# Brainb.net
KiCad netlist of a schematic drawn in EAGLE
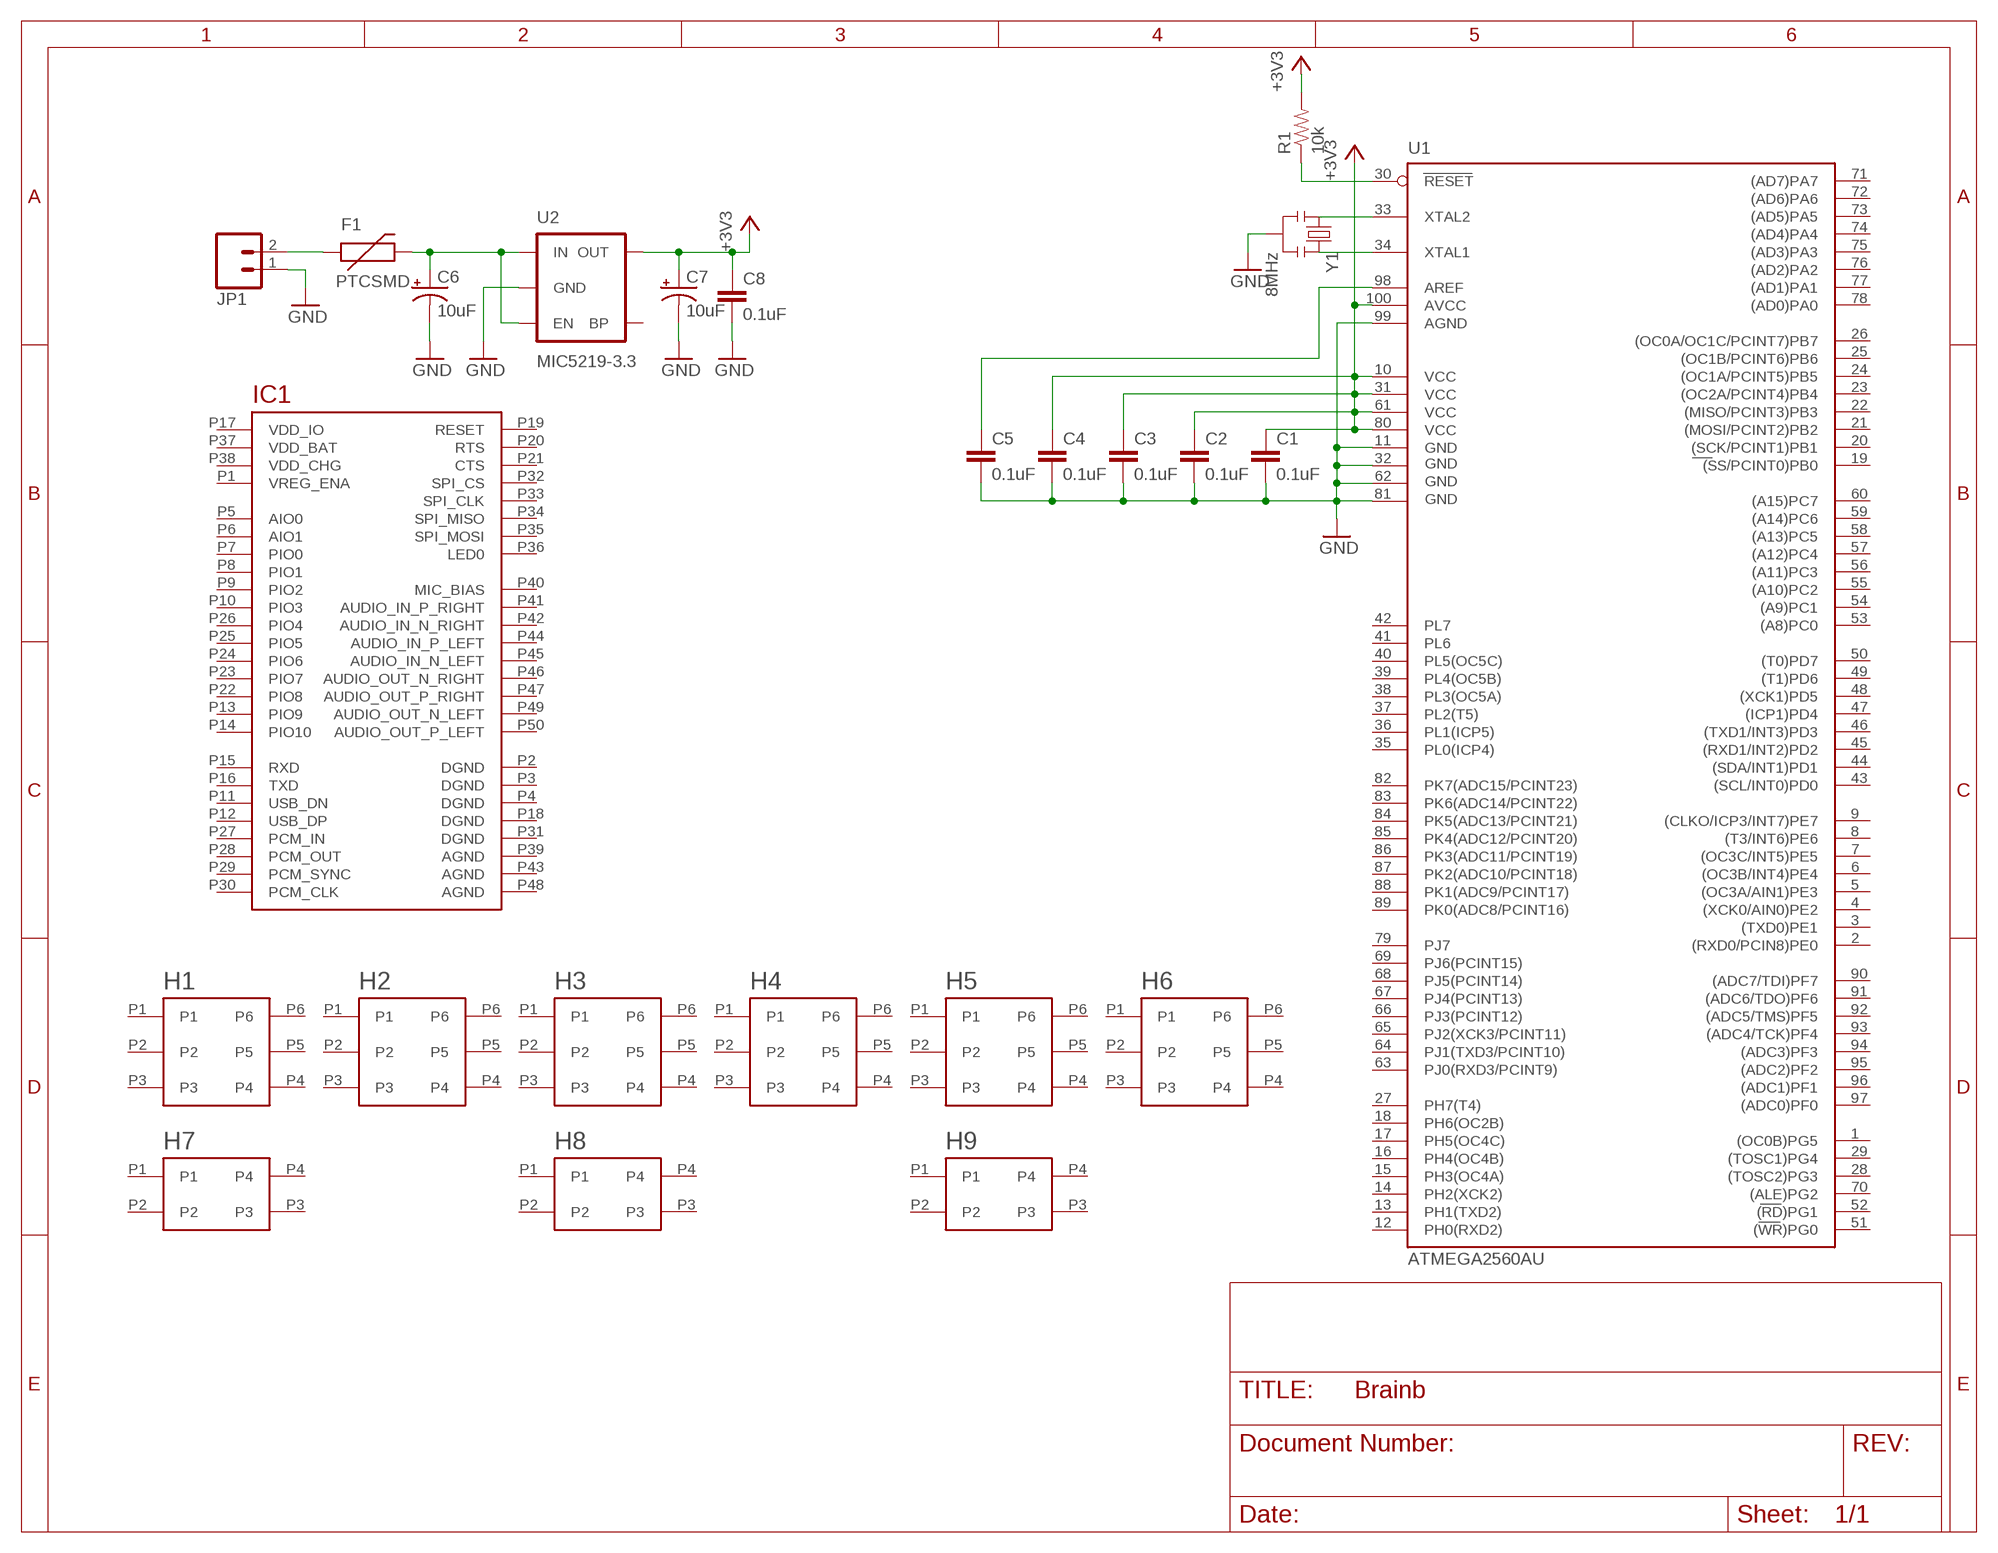
[diagram p0: schematic, sheet 1]

(export (version "E")
  (design (tool "Eeschema 10.0.6"))
  (components
    (comp (ref "C1")
      (value "0.1uF")
      (footprint "eagle-import:0603-CAP")
      (libsource (lib "eagle-import") (part "CAP0603-CAP"))
    )
    (comp (ref "C2")
      (value "0.1uF")
      (footprint "eagle-import:0603-CAP")
      (libsource (lib "eagle-import") (part "CAP0603-CAP"))
    )
    (comp (ref "C3")
      (value "0.1uF")
      (footprint "eagle-import:0603-CAP")
      (libsource (lib "eagle-import") (part "CAP0603-CAP"))
    )
    (comp (ref "C4")
      (value "0.1uF")
      (footprint "eagle-import:0603-CAP")
      (libsource (lib "eagle-import") (part "CAP0603-CAP"))
    )
    (comp (ref "C5")
      (value "0.1uF")
      (footprint "eagle-import:0603-CAP")
      (libsource (lib "eagle-import") (part "CAP0603-CAP"))
    )
    (comp (ref "C6")
      (value "10uF")
      (footprint "eagle-import:EIA3216")
      (libsource (lib "eagle-import") (part "CAP_POL1206"))
    )
    (comp (ref "C7")
      (value "10uF")
      (footprint "eagle-import:EIA3216")
      (libsource (lib "eagle-import") (part "CAP_POL1206"))
    )
    (comp (ref "C8")
      (value "0.1uF")
      (footprint "eagle-import:0603-CAP")
      (libsource (lib "eagle-import") (part "CAP0603-CAP"))
    )
    (comp (ref "F1")
      (value "PTCSMD")
      (footprint "eagle-import:PTC-1206")
      (libsource (lib "eagle-import") (part "PTCSMD"))
    )
    (comp (ref "H1")
      (value "3X2F_1MM_SMD")
      (footprint "eagle-import:3X2F_1MM_SMD")
      (libsource (lib "eagle-import") (part "3X2F_1MM_SMD"))
    )
    (comp (ref "H2")
      (value "3X2F_1MM_SMD")
      (footprint "eagle-import:3X2F_1MM_SMD")
      (libsource (lib "eagle-import") (part "3X2F_1MM_SMD"))
    )
    (comp (ref "H3")
      (value "3X2F_1MM_SMD")
      (footprint "eagle-import:3X2F_1MM_SMD")
      (libsource (lib "eagle-import") (part "3X2F_1MM_SMD"))
    )
    (comp (ref "H4")
      (value "3X2F_1MM_SMD")
      (footprint "eagle-import:3X2F_1MM_SMD")
      (libsource (lib "eagle-import") (part "3X2F_1MM_SMD"))
    )
    (comp (ref "H5")
      (value "3X2F_1MM_SMD")
      (footprint "eagle-import:3X2F_1MM_SMD")
      (libsource (lib "eagle-import") (part "3X2F_1MM_SMD"))
    )
    (comp (ref "H6")
      (value "3X2F_1MM_SMD")
      (footprint "eagle-import:3X2F_1MM_SMD")
      (libsource (lib "eagle-import") (part "3X2F_1MM_SMD"))
    )
    (comp (ref "H7")
      (value "2X2F_1MM_SMD")
      (footprint "eagle-import:2X2F_1MM_SMD")
      (libsource (lib "eagle-import") (part "2X2F_1MM_SMD"))
    )
    (comp (ref "H8")
      (value "2X2F_1MM_SMD")
      (footprint "eagle-import:2X2F_1MM_SMD")
      (libsource (lib "eagle-import") (part "2X2F_1MM_SMD"))
    )
    (comp (ref "H9")
      (value "2X2F_1MM_SMD")
      (footprint "eagle-import:2X2F_1MM_SMD")
      (libsource (lib "eagle-import") (part "2X2F_1MM_SMD"))
    )
    (comp (ref "IC1")
      (value "WT32WT32")
      (footprint "eagle-import:WT32")
      (libsource (lib "eagle-import") (part "WT32WT32"))
    )
    (comp (ref "JP1")
      (value "M02-JST-2MM-SMT")
      (footprint "eagle-import:JST-2-SMD")
      (libsource (lib "eagle-import") (part "M02-JST-2MM-SMT"))
    )
    (comp (ref "R1")
      (value "10k")
      (footprint "eagle-import:0603-RES")
      (libsource (lib "eagle-import") (part "RESISTOR0603-RES"))
    )
    (comp (ref "U1")
      (value "ATMEGA2560AU")
      (footprint "eagle-import:TQFP100")
      (libsource (lib "eagle-import") (part "ATMEGA2560AU"))
    )
    (comp (ref "U2")
      (value "MIC5219-3.3")
      (footprint "eagle-import:SOT23-5")
      (libsource (lib "eagle-import") (part "V_REG_MIC5219SMD"))
    )
    (comp (ref "Y1")
      (value "8MHz")
      (footprint "eagle-import:RESONATOR-SMD")
      (libsource (lib "eagle-import") (part "RESONATORSMD"))
    )
  )
  (nets
    (net (code "1") (name "+3V3") (class "Default")
      (node (ref "C1") (pin "1") (pinfunction "1_1") (pintype "passive"))
      (node (ref "C2") (pin "1") (pinfunction "1_1") (pintype "passive"))
      (node (ref "C3") (pin "1") (pinfunction "1_1") (pintype "passive"))
      (node (ref "C4") (pin "1") (pinfunction "1_1") (pintype "passive"))
      (node (ref "C7") (pin "A") (pinfunction "+_A") (pintype "passive"))
      (node (ref "C8") (pin "1") (pinfunction "1_1") (pintype "passive"))
      (node (ref "R1") (pin "2") (pinfunction "2_2") (pintype "passive"))
      (node (ref "U1") (pin "10") (pinfunction "VCC_10") (pintype "power_in"))
      (node (ref "U1") (pin "100") (pinfunction "AVCC_100") (pintype "power_in"))
      (node (ref "U1") (pin "31") (pinfunction "VCC1_31") (pintype "power_in"))
      (node (ref "U1") (pin "61") (pinfunction "VCC2_61") (pintype "power_in"))
      (node (ref "U1") (pin "80") (pinfunction "VCC3_80") (pintype "power_in"))
      (node (ref "U2") (pin "5") (pinfunction "OUT_5") (pintype "passive"))
    )
    (net (code "2") (name "GND") (class "Default")
      (node (ref "C1") (pin "2") (pinfunction "2_2") (pintype "passive"))
      (node (ref "C2") (pin "2") (pinfunction "2_2") (pintype "passive"))
      (node (ref "C3") (pin "2") (pinfunction "2_2") (pintype "passive"))
      (node (ref "C4") (pin "2") (pinfunction "2_2") (pintype "passive"))
      (node (ref "C5") (pin "2") (pinfunction "2_2") (pintype "passive"))
      (node (ref "C6") (pin "C") (pinfunction "-_C") (pintype "passive"))
      (node (ref "C7") (pin "C") (pinfunction "-_C") (pintype "passive"))
      (node (ref "C8") (pin "2") (pinfunction "2_2") (pintype "passive"))
      (node (ref "JP1") (pin "1") (pinfunction "2_1") (pintype "passive"))
      (node (ref "U1") (pin "11") (pinfunction "GND_11") (pintype "power_in"))
      (node (ref "U1") (pin "32") (pinfunction "GND1_32") (pintype "power_in"))
      (node (ref "U1") (pin "62") (pinfunction "GND2_62") (pintype "power_in"))
      (node (ref "U1") (pin "81") (pinfunction "GND3_81") (pintype "power_in"))
      (node (ref "U1") (pin "99") (pinfunction "AGND_99") (pintype "power_in"))
      (node (ref "U2") (pin "2") (pinfunction "GND_2") (pintype "input"))
      (node (ref "Y1") (pin "2") (pinfunction "2_2") (pintype "passive"))
    )
    (net (code "3") (name "Net-(C6-+)") (class "Default")
      (node (ref "C6") (pin "A") (pinfunction "+_A") (pintype "passive"))
      (node (ref "F1") (pin "2") (pinfunction "2_2") (pintype "bidirectional"))
      (node (ref "U2") (pin "1") (pinfunction "IN_1") (pintype "input"))
      (node (ref "U2") (pin "3") (pinfunction "EN_3") (pintype "input"))
    )
    (net (code "4") (name "Net-(JP1-1)") (class "Default")
      (node (ref "F1") (pin "1") (pinfunction "1_1") (pintype "bidirectional"))
      (node (ref "JP1") (pin "2") (pinfunction "1_2") (pintype "passive"))
    )
    (net (code "5") (name "Net-(U1-AREF)") (class "Default")
      (node (ref "C5") (pin "1") (pinfunction "1_1") (pintype "passive"))
      (node (ref "U1") (pin "98") (pinfunction "AREF_98") (pintype "bidirectional"))
    )
    (net (code "6") (name "Net-(U1-RESET)") (class "Default")
      (node (ref "R1") (pin "1") (pinfunction "1_1") (pintype "passive"))
      (node (ref "U1") (pin "30") (pinfunction "RESET_30") (pintype "input"))
    )
    (net (code "7") (name "Net-(U1-XTAL1)") (class "Default")
      (node (ref "U1") (pin "34") (pinfunction "XTAL1_34") (pintype "input"))
      (node (ref "Y1") (pin "3") (pinfunction "3_3") (pintype "passive"))
    )
    (net (code "8") (name "Net-(U1-XTAL2)") (class "Default")
      (node (ref "U1") (pin "33") (pinfunction "XTAL2_33") (pintype "output"))
      (node (ref "Y1") (pin "1") (pinfunction "1_1") (pintype "passive"))
    )
    (net (code "9") (name "unconnected-(H1-PadP1)") (class "Default")
      (node (ref "H1") (pin "P1") (pinfunction "P1_P1") (pintype "bidirectional"))
    )
    (net (code "10") (name "unconnected-(H1-PadP2)") (class "Default")
      (node (ref "H1") (pin "P2") (pinfunction "P2_P2") (pintype "bidirectional"))
    )
    (net (code "11") (name "unconnected-(H1-PadP3)") (class "Default")
      (node (ref "H1") (pin "P3") (pinfunction "P3_P3") (pintype "bidirectional"))
    )
    (net (code "12") (name "unconnected-(H1-PadP4)") (class "Default")
      (node (ref "H1") (pin "P4") (pinfunction "P4_P4") (pintype "bidirectional"))
    )
    (net (code "13") (name "unconnected-(H1-PadP5)") (class "Default")
      (node (ref "H1") (pin "P5") (pinfunction "P5_P5") (pintype "bidirectional"))
    )
    (net (code "14") (name "unconnected-(H1-PadP6)") (class "Default")
      (node (ref "H1") (pin "P6") (pinfunction "P6_P6") (pintype "bidirectional"))
    )
    (net (code "15") (name "unconnected-(H2-PadP1)") (class "Default")
      (node (ref "H2") (pin "P1") (pinfunction "P1_P1") (pintype "bidirectional"))
    )
    (net (code "16") (name "unconnected-(H2-PadP2)") (class "Default")
      (node (ref "H2") (pin "P2") (pinfunction "P2_P2") (pintype "bidirectional"))
    )
    (net (code "17") (name "unconnected-(H2-PadP3)") (class "Default")
      (node (ref "H2") (pin "P3") (pinfunction "P3_P3") (pintype "bidirectional"))
    )
    (net (code "18") (name "unconnected-(H2-PadP4)") (class "Default")
      (node (ref "H2") (pin "P4") (pinfunction "P4_P4") (pintype "bidirectional"))
    )
    (net (code "19") (name "unconnected-(H2-PadP5)") (class "Default")
      (node (ref "H2") (pin "P5") (pinfunction "P5_P5") (pintype "bidirectional"))
    )
    (net (code "20") (name "unconnected-(H2-PadP6)") (class "Default")
      (node (ref "H2") (pin "P6") (pinfunction "P6_P6") (pintype "bidirectional"))
    )
    (net (code "21") (name "unconnected-(H3-PadP1)") (class "Default")
      (node (ref "H3") (pin "P1") (pinfunction "P1_P1") (pintype "bidirectional"))
    )
    (net (code "22") (name "unconnected-(H3-PadP2)") (class "Default")
      (node (ref "H3") (pin "P2") (pinfunction "P2_P2") (pintype "bidirectional"))
    )
    (net (code "23") (name "unconnected-(H3-PadP3)") (class "Default")
      (node (ref "H3") (pin "P3") (pinfunction "P3_P3") (pintype "bidirectional"))
    )
    (net (code "24") (name "unconnected-(H3-PadP4)") (class "Default")
      (node (ref "H3") (pin "P4") (pinfunction "P4_P4") (pintype "bidirectional"))
    )
    (net (code "25") (name "unconnected-(H3-PadP5)") (class "Default")
      (node (ref "H3") (pin "P5") (pinfunction "P5_P5") (pintype "bidirectional"))
    )
    (net (code "26") (name "unconnected-(H3-PadP6)") (class "Default")
      (node (ref "H3") (pin "P6") (pinfunction "P6_P6") (pintype "bidirectional"))
    )
    (net (code "27") (name "unconnected-(H4-PadP1)") (class "Default")
      (node (ref "H4") (pin "P1") (pinfunction "P1_P1") (pintype "bidirectional"))
    )
    (net (code "28") (name "unconnected-(H4-PadP2)") (class "Default")
      (node (ref "H4") (pin "P2") (pinfunction "P2_P2") (pintype "bidirectional"))
    )
    (net (code "29") (name "unconnected-(H4-PadP3)") (class "Default")
      (node (ref "H4") (pin "P3") (pinfunction "P3_P3") (pintype "bidirectional"))
    )
    (net (code "30") (name "unconnected-(H4-PadP4)") (class "Default")
      (node (ref "H4") (pin "P4") (pinfunction "P4_P4") (pintype "bidirectional"))
    )
    (net (code "31") (name "unconnected-(H4-PadP5)") (class "Default")
      (node (ref "H4") (pin "P5") (pinfunction "P5_P5") (pintype "bidirectional"))
    )
    (net (code "32") (name "unconnected-(H4-PadP6)") (class "Default")
      (node (ref "H4") (pin "P6") (pinfunction "P6_P6") (pintype "bidirectional"))
    )
    (net (code "33") (name "unconnected-(H5-PadP1)") (class "Default")
      (node (ref "H5") (pin "P1") (pinfunction "P1_P1") (pintype "bidirectional"))
    )
    (net (code "34") (name "unconnected-(H5-PadP2)") (class "Default")
      (node (ref "H5") (pin "P2") (pinfunction "P2_P2") (pintype "bidirectional"))
    )
    (net (code "35") (name "unconnected-(H5-PadP3)") (class "Default")
      (node (ref "H5") (pin "P3") (pinfunction "P3_P3") (pintype "bidirectional"))
    )
    (net (code "36") (name "unconnected-(H5-PadP4)") (class "Default")
      (node (ref "H5") (pin "P4") (pinfunction "P4_P4") (pintype "bidirectional"))
    )
    (net (code "37") (name "unconnected-(H5-PadP5)") (class "Default")
      (node (ref "H5") (pin "P5") (pinfunction "P5_P5") (pintype "bidirectional"))
    )
    (net (code "38") (name "unconnected-(H5-PadP6)") (class "Default")
      (node (ref "H5") (pin "P6") (pinfunction "P6_P6") (pintype "bidirectional"))
    )
    (net (code "39") (name "unconnected-(H6-PadP1)") (class "Default")
      (node (ref "H6") (pin "P1") (pinfunction "P1_P1") (pintype "bidirectional"))
    )
    (net (code "40") (name "unconnected-(H6-PadP2)") (class "Default")
      (node (ref "H6") (pin "P2") (pinfunction "P2_P2") (pintype "bidirectional"))
    )
    (net (code "41") (name "unconnected-(H6-PadP3)") (class "Default")
      (node (ref "H6") (pin "P3") (pinfunction "P3_P3") (pintype "bidirectional"))
    )
    (net (code "42") (name "unconnected-(H6-PadP4)") (class "Default")
      (node (ref "H6") (pin "P4") (pinfunction "P4_P4") (pintype "bidirectional"))
    )
    (net (code "43") (name "unconnected-(H6-PadP5)") (class "Default")
      (node (ref "H6") (pin "P5") (pinfunction "P5_P5") (pintype "bidirectional"))
    )
    (net (code "44") (name "unconnected-(H6-PadP6)") (class "Default")
      (node (ref "H6") (pin "P6") (pinfunction "P6_P6") (pintype "bidirectional"))
    )
    (net (code "45") (name "unconnected-(H7-PadP1)") (class "Default")
      (node (ref "H7") (pin "P1") (pinfunction "P1_P1") (pintype "bidirectional"))
    )
    (net (code "46") (name "unconnected-(H7-PadP2)") (class "Default")
      (node (ref "H7") (pin "P2") (pinfunction "P2_P2") (pintype "bidirectional"))
    )
    (net (code "47") (name "unconnected-(H7-PadP3)") (class "Default")
      (node (ref "H7") (pin "P3") (pinfunction "P3_P3") (pintype "bidirectional"))
    )
    (net (code "48") (name "unconnected-(H7-PadP4)") (class "Default")
      (node (ref "H7") (pin "P4") (pinfunction "P4_P4") (pintype "bidirectional"))
    )
    (net (code "49") (name "unconnected-(H8-PadP1)") (class "Default")
      (node (ref "H8") (pin "P1") (pinfunction "P1_P1") (pintype "bidirectional"))
    )
    (net (code "50") (name "unconnected-(H8-PadP2)") (class "Default")
      (node (ref "H8") (pin "P2") (pinfunction "P2_P2") (pintype "bidirectional"))
    )
    (net (code "51") (name "unconnected-(H8-PadP3)") (class "Default")
      (node (ref "H8") (pin "P3") (pinfunction "P3_P3") (pintype "bidirectional"))
    )
    (net (code "52") (name "unconnected-(H8-PadP4)") (class "Default")
      (node (ref "H8") (pin "P4") (pinfunction "P4_P4") (pintype "bidirectional"))
    )
    (net (code "53") (name "unconnected-(H9-PadP1)") (class "Default")
      (node (ref "H9") (pin "P1") (pinfunction "P1_P1") (pintype "bidirectional"))
    )
    (net (code "54") (name "unconnected-(H9-PadP2)") (class "Default")
      (node (ref "H9") (pin "P2") (pinfunction "P2_P2") (pintype "bidirectional"))
    )
    (net (code "55") (name "unconnected-(H9-PadP3)") (class "Default")
      (node (ref "H9") (pin "P3") (pinfunction "P3_P3") (pintype "bidirectional"))
    )
    (net (code "56") (name "unconnected-(H9-PadP4)") (class "Default")
      (node (ref "H9") (pin "P4") (pinfunction "P4_P4") (pintype "bidirectional"))
    )
    (net (code "57") (name "unconnected-(IC1-AGND-PadP39)") (class "Default")
      (node (ref "IC1") (pin "P39") (pinfunction "AGND_P39") (pintype "bidirectional"))
    )
    (net (code "58") (name "unconnected-(IC1-AGND-PadP43)") (class "Default")
      (node (ref "IC1") (pin "P43") (pinfunction "AGND_P43") (pintype "bidirectional"))
    )
    (net (code "59") (name "unconnected-(IC1-AGND-PadP48)") (class "Default")
      (node (ref "IC1") (pin "P48") (pinfunction "AGND_P48") (pintype "bidirectional"))
    )
    (net (code "60") (name "unconnected-(IC1-AIO0-PadP5)") (class "Default")
      (node (ref "IC1") (pin "P5") (pinfunction "AIO0_P5") (pintype "bidirectional"))
    )
    (net (code "61") (name "unconnected-(IC1-AIO1-PadP6)") (class "Default")
      (node (ref "IC1") (pin "P6") (pinfunction "AIO1_P6") (pintype "bidirectional"))
    )
    (net (code "62") (name "unconnected-(IC1-AUDIO_IN_N_LEFT-PadP45)") (class "Default")
      (node (ref "IC1") (pin "P45") (pinfunction "AUDIO_IN_N_LEFT_P45") (pintype "bidirectional"))
    )
    (net (code "63") (name "unconnected-(IC1-AUDIO_IN_N_RIGHT-PadP42)") (class "Default")
      (node (ref "IC1") (pin "P42") (pinfunction "AUDIO_IN_N_RIGHT_P42") (pintype "bidirectional"))
    )
    (net (code "64") (name "unconnected-(IC1-AUDIO_IN_P_LEFT-PadP44)") (class "Default")
      (node (ref "IC1") (pin "P44") (pinfunction "AUDIO_IN_P_LEFT_P44") (pintype "bidirectional"))
    )
    (net (code "65") (name "unconnected-(IC1-AUDIO_IN_P_RIGHT-PadP41)") (class "Default")
      (node (ref "IC1") (pin "P41") (pinfunction "AUDIO_IN_P_RIGHT_P41") (pintype "bidirectional"))
    )
    (net (code "66") (name "unconnected-(IC1-AUDIO_OUT_N_LEFT-PadP49)") (class "Default")
      (node (ref "IC1") (pin "P49") (pinfunction "AUDIO_OUT_N_LEFT_P49") (pintype "bidirectional"))
    )
    (net (code "67") (name "unconnected-(IC1-AUDIO_OUT_N_RIGHT-PadP46)") (class "Default")
      (node (ref "IC1") (pin "P46") (pinfunction "AUDIO_OUT_N_RIGHT_P46") (pintype "bidirectional"))
    )
    (net (code "68") (name "unconnected-(IC1-AUDIO_OUT_P_LEFT-PadP50)") (class "Default")
      (node (ref "IC1") (pin "P50") (pinfunction "AUDIO_OUT_P_LEFT_P50") (pintype "bidirectional"))
    )
    (net (code "69") (name "unconnected-(IC1-AUDIO_OUT_P_RIGHT-PadP47)") (class "Default")
      (node (ref "IC1") (pin "P47") (pinfunction "AUDIO_OUT_P_RIGHT_P47") (pintype "bidirectional"))
    )
    (net (code "70") (name "unconnected-(IC1-CTS-PadP21)") (class "Default")
      (node (ref "IC1") (pin "P21") (pinfunction "CTS_P21") (pintype "bidirectional"))
    )
    (net (code "71") (name "unconnected-(IC1-DGND-PadP2)") (class "Default")
      (node (ref "IC1") (pin "P2") (pinfunction "DGND_P2") (pintype "bidirectional"))
    )
    (net (code "72") (name "unconnected-(IC1-DGND-PadP3)") (class "Default")
      (node (ref "IC1") (pin "P3") (pinfunction "DGND_P3") (pintype "bidirectional"))
    )
    (net (code "73") (name "unconnected-(IC1-DGND-PadP4)") (class "Default")
      (node (ref "IC1") (pin "P4") (pinfunction "DGND_P4") (pintype "bidirectional"))
    )
    (net (code "74") (name "unconnected-(IC1-DGND-PadP18)") (class "Default")
      (node (ref "IC1") (pin "P18") (pinfunction "DGND_P18") (pintype "bidirectional"))
    )
    (net (code "75") (name "unconnected-(IC1-DGND-PadP31)") (class "Default")
      (node (ref "IC1") (pin "P31") (pinfunction "DGND_P31") (pintype "bidirectional"))
    )
    (net (code "76") (name "unconnected-(IC1-LED0-PadP36)") (class "Default")
      (node (ref "IC1") (pin "P36") (pinfunction "LED0_P36") (pintype "bidirectional"))
    )
    (net (code "77") (name "unconnected-(IC1-MIC_BIAS-PadP40)") (class "Default")
      (node (ref "IC1") (pin "P40") (pinfunction "MIC_BIAS_P40") (pintype "bidirectional"))
    )
    (net (code "78") (name "unconnected-(IC1-PCM_CLK-PadP30)") (class "Default")
      (node (ref "IC1") (pin "P30") (pinfunction "PCM_CLK_P30") (pintype "bidirectional"))
    )
    (net (code "79") (name "unconnected-(IC1-PCM_IN-PadP27)") (class "Default")
      (node (ref "IC1") (pin "P27") (pinfunction "PCM_IN_P27") (pintype "bidirectional"))
    )
    (net (code "80") (name "unconnected-(IC1-PCM_OUT-PadP28)") (class "Default")
      (node (ref "IC1") (pin "P28") (pinfunction "PCM_OUT_P28") (pintype "bidirectional"))
    )
    (net (code "81") (name "unconnected-(IC1-PCM_SYNC-PadP29)") (class "Default")
      (node (ref "IC1") (pin "P29") (pinfunction "PCM_SYNC_P29") (pintype "bidirectional"))
    )
    (net (code "82") (name "unconnected-(IC1-PIO0-PadP7)") (class "Default")
      (node (ref "IC1") (pin "P7") (pinfunction "PIO0_P7") (pintype "bidirectional"))
    )
    (net (code "83") (name "unconnected-(IC1-PIO1-PadP8)") (class "Default")
      (node (ref "IC1") (pin "P8") (pinfunction "PIO1_P8") (pintype "bidirectional"))
    )
    (net (code "84") (name "unconnected-(IC1-PIO2-PadP9)") (class "Default")
      (node (ref "IC1") (pin "P9") (pinfunction "PIO2_P9") (pintype "bidirectional"))
    )
    (net (code "85") (name "unconnected-(IC1-PIO3-PadP10)") (class "Default")
      (node (ref "IC1") (pin "P10") (pinfunction "PIO3_P10") (pintype "bidirectional"))
    )
    (net (code "86") (name "unconnected-(IC1-PIO4-PadP26)") (class "Default")
      (node (ref "IC1") (pin "P26") (pinfunction "PIO4_P26") (pintype "bidirectional"))
    )
    (net (code "87") (name "unconnected-(IC1-PIO5-PadP25)") (class "Default")
      (node (ref "IC1") (pin "P25") (pinfunction "PIO5_P25") (pintype "bidirectional"))
    )
    (net (code "88") (name "unconnected-(IC1-PIO6-PadP24)") (class "Default")
      (node (ref "IC1") (pin "P24") (pinfunction "PIO6_P24") (pintype "bidirectional"))
    )
    (net (code "89") (name "unconnected-(IC1-PIO7-PadP23)") (class "Default")
      (node (ref "IC1") (pin "P23") (pinfunction "PIO7_P23") (pintype "bidirectional"))
    )
    (net (code "90") (name "unconnected-(IC1-PIO8-PadP22)") (class "Default")
      (node (ref "IC1") (pin "P22") (pinfunction "PIO8_P22") (pintype "bidirectional"))
    )
    (net (code "91") (name "unconnected-(IC1-PIO9-PadP13)") (class "Default")
      (node (ref "IC1") (pin "P13") (pinfunction "PIO9_P13") (pintype "bidirectional"))
    )
    (net (code "92") (name "unconnected-(IC1-PIO10-PadP14)") (class "Default")
      (node (ref "IC1") (pin "P14") (pinfunction "PIO10_P14") (pintype "bidirectional"))
    )
    (net (code "93") (name "unconnected-(IC1-RESET-PadP19)") (class "Default")
      (node (ref "IC1") (pin "P19") (pinfunction "RESET_P19") (pintype "bidirectional"))
    )
    (net (code "94") (name "unconnected-(IC1-RTS-PadP20)") (class "Default")
      (node (ref "IC1") (pin "P20") (pinfunction "RTS_P20") (pintype "bidirectional"))
    )
    (net (code "95") (name "unconnected-(IC1-RXD-PadP15)") (class "Default")
      (node (ref "IC1") (pin "P15") (pinfunction "RXD_P15") (pintype "bidirectional"))
    )
    (net (code "96") (name "unconnected-(IC1-SPI_CLK-PadP33)") (class "Default")
      (node (ref "IC1") (pin "P33") (pinfunction "SPI_CLK_P33") (pintype "bidirectional"))
    )
    (net (code "97") (name "unconnected-(IC1-SPI_CS-PadP32)") (class "Default")
      (node (ref "IC1") (pin "P32") (pinfunction "SPI_CS_P32") (pintype "bidirectional"))
    )
    (net (code "98") (name "unconnected-(IC1-SPI_MISO-PadP34)") (class "Default")
      (node (ref "IC1") (pin "P34") (pinfunction "SPI_MISO_P34") (pintype "bidirectional"))
    )
    (net (code "99") (name "unconnected-(IC1-SPI_MOSI-PadP35)") (class "Default")
      (node (ref "IC1") (pin "P35") (pinfunction "SPI_MOSI_P35") (pintype "bidirectional"))
    )
    (net (code "100") (name "unconnected-(IC1-TXD-PadP16)") (class "Default")
      (node (ref "IC1") (pin "P16") (pinfunction "TXD_P16") (pintype "bidirectional"))
    )
    (net (code "101") (name "unconnected-(IC1-USB_DN-PadP11)") (class "Default")
      (node (ref "IC1") (pin "P11") (pinfunction "USB_DN_P11") (pintype "bidirectional"))
    )
    (net (code "102") (name "unconnected-(IC1-USB_DP-PadP12)") (class "Default")
      (node (ref "IC1") (pin "P12") (pinfunction "USB_DP_P12") (pintype "bidirectional"))
    )
    (net (code "103") (name "unconnected-(IC1-VDD_BAT-PadP37)") (class "Default")
      (node (ref "IC1") (pin "P37") (pinfunction "VDD_BAT_P37") (pintype "bidirectional"))
    )
    (net (code "104") (name "unconnected-(IC1-VDD_CHG-PadP38)") (class "Default")
      (node (ref "IC1") (pin "P38") (pinfunction "VDD_CHG_P38") (pintype "bidirectional"))
    )
    (net (code "105") (name "unconnected-(IC1-VDD_IO-PadP17)") (class "Default")
      (node (ref "IC1") (pin "P17") (pinfunction "VDD_IO_P17") (pintype "bidirectional"))
    )
    (net (code "106") (name "unconnected-(IC1-VREG_ENA-PadP1)") (class "Default")
      (node (ref "IC1") (pin "P1") (pinfunction "VREG_ENA_P1") (pintype "bidirectional"))
    )
    (net (code "107") (name "unconnected-(U1-(A8)PC0-Pad53)") (class "Default")
      (node (ref "U1") (pin "53") (pinfunction "(A8)PC0_53") (pintype "bidirectional"))
    )
    (net (code "108") (name "unconnected-(U1-(A9)PC1-Pad54)") (class "Default")
      (node (ref "U1") (pin "54") (pinfunction "(A9)PC1_54") (pintype "bidirectional"))
    )
    (net (code "109") (name "unconnected-(U1-(A10)PC2-Pad55)") (class "Default")
      (node (ref "U1") (pin "55") (pinfunction "(A10)PC2_55") (pintype "bidirectional"))
    )
    (net (code "110") (name "unconnected-(U1-(A11)PC3-Pad56)") (class "Default")
      (node (ref "U1") (pin "56") (pinfunction "(A11)PC3_56") (pintype "bidirectional"))
    )
    (net (code "111") (name "unconnected-(U1-(A12)PC4-Pad57)") (class "Default")
      (node (ref "U1") (pin "57") (pinfunction "(A12)PC4_57") (pintype "bidirectional"))
    )
    (net (code "112") (name "unconnected-(U1-(A13)PC5-Pad58)") (class "Default")
      (node (ref "U1") (pin "58") (pinfunction "(A13)PC5_58") (pintype "bidirectional"))
    )
    (net (code "113") (name "unconnected-(U1-(A14)PC6-Pad59)") (class "Default")
      (node (ref "U1") (pin "59") (pinfunction "(A14)PC6_59") (pintype "bidirectional"))
    )
    (net (code "114") (name "unconnected-(U1-(A15)PC7-Pad60)") (class "Default")
      (node (ref "U1") (pin "60") (pinfunction "(A15)PC7_60") (pintype "bidirectional"))
    )
    (net (code "115") (name "unconnected-(U1-(AD0)PA0-Pad78)") (class "Default")
      (node (ref "U1") (pin "78") (pinfunction "(AD0)PA0_78") (pintype "bidirectional"))
    )
    (net (code "116") (name "unconnected-(U1-(AD1)PA1-Pad77)") (class "Default")
      (node (ref "U1") (pin "77") (pinfunction "(AD1)PA1_77") (pintype "bidirectional"))
    )
    (net (code "117") (name "unconnected-(U1-(AD2)PA2-Pad76)") (class "Default")
      (node (ref "U1") (pin "76") (pinfunction "(AD2)PA2_76") (pintype "bidirectional"))
    )
    (net (code "118") (name "unconnected-(U1-(AD3)PA3-Pad75)") (class "Default")
      (node (ref "U1") (pin "75") (pinfunction "(AD3)PA3_75") (pintype "bidirectional"))
    )
    (net (code "119") (name "unconnected-(U1-(AD4)PA4-Pad74)") (class "Default")
      (node (ref "U1") (pin "74") (pinfunction "(AD4)PA4_74") (pintype "bidirectional"))
    )
    (net (code "120") (name "unconnected-(U1-(AD5)PA5-Pad73)") (class "Default")
      (node (ref "U1") (pin "73") (pinfunction "(AD5)PA5_73") (pintype "bidirectional"))
    )
    (net (code "121") (name "unconnected-(U1-(AD6)PA6-Pad72)") (class "Default")
      (node (ref "U1") (pin "72") (pinfunction "(AD6)PA6_72") (pintype "bidirectional"))
    )
    (net (code "122") (name "unconnected-(U1-(AD7)PA7-Pad71)") (class "Default")
      (node (ref "U1") (pin "71") (pinfunction "(AD7)PA7_71") (pintype "bidirectional"))
    )
    (net (code "123") (name "unconnected-(U1-(ADC0)PF0-Pad97)") (class "Default")
      (node (ref "U1") (pin "97") (pinfunction "(ADC0)PF0_97") (pintype "bidirectional"))
    )
    (net (code "124") (name "unconnected-(U1-(ADC1)PF1-Pad96)") (class "Default")
      (node (ref "U1") (pin "96") (pinfunction "(ADC1)PF1_96") (pintype "bidirectional"))
    )
    (net (code "125") (name "unconnected-(U1-(ADC2)PF2-Pad95)") (class "Default")
      (node (ref "U1") (pin "95") (pinfunction "(ADC2)PF2_95") (pintype "bidirectional"))
    )
    (net (code "126") (name "unconnected-(U1-(ADC3)PF3-Pad94)") (class "Default")
      (node (ref "U1") (pin "94") (pinfunction "(ADC3)PF3_94") (pintype "bidirectional"))
    )
    (net (code "127") (name "unconnected-(U1-(ADC4{slash}TCK)PF4-Pad93)") (class "Default")
      (node (ref "U1") (pin "93") (pinfunction "(ADC4/TCK)PF4_93") (pintype "bidirectional"))
    )
    (net (code "128") (name "unconnected-(U1-(ADC5{slash}TMS)PF5-Pad92)") (class "Default")
      (node (ref "U1") (pin "92") (pinfunction "(ADC5/TMS)PF5_92") (pintype "bidirectional"))
    )
    (net (code "129") (name "unconnected-(U1-(ADC6{slash}TDO)PF6-Pad91)") (class "Default")
      (node (ref "U1") (pin "91") (pinfunction "(ADC6/TDO)PF6_91") (pintype "bidirectional"))
    )
    (net (code "130") (name "unconnected-(U1-(ADC7{slash}TDI)PF7-Pad90)") (class "Default")
      (node (ref "U1") (pin "90") (pinfunction "(ADC7/TDI)PF7_90") (pintype "bidirectional"))
    )
    (net (code "131") (name "unconnected-(U1-(ALE)PG2-Pad70)") (class "Default")
      (node (ref "U1") (pin "70") (pinfunction "(ALE)PG2_70") (pintype "bidirectional"))
    )
    (net (code "132") (name "unconnected-(U1-(CLKO{slash}ICP3{slash}INT7)PE7-Pad9)") (class "Default")
      (node (ref "U1") (pin "9") (pinfunction "(CLKO/ICP3/INT7)PE7_9") (pintype "bidirectional"))
    )
    (net (code "133") (name "unconnected-(U1-(ICP1)PD4-Pad47)") (class "Default")
      (node (ref "U1") (pin "47") (pinfunction "(ICP1)PD4_47") (pintype "bidirectional"))
    )
    (net (code "134") (name "unconnected-(U1-(MISO{slash}PCINT3)PB3-Pad22)") (class "Default")
      (node (ref "U1") (pin "22") (pinfunction "(MISO/PCINT3)PB3_22") (pintype "bidirectional"))
    )
    (net (code "135") (name "unconnected-(U1-(MOSI{slash}PCINT2)PB2-Pad21)") (class "Default")
      (node (ref "U1") (pin "21") (pinfunction "(MOSI/PCINT2)PB2_21") (pintype "bidirectional"))
    )
    (net (code "136") (name "unconnected-(U1-(OC0A{slash}OC1C{slash}PCINT7)PB7-Pad26)") (class "Default")
      (node (ref "U1") (pin "26") (pinfunction "(OC0A/OC1C/PCINT7)PB7_26") (pintype "bidirectional"))
    )
    (net (code "137") (name "unconnected-(U1-(OC0B)PG5-Pad1)") (class "Default")
      (node (ref "U1") (pin "1") (pinfunction "(OC0B)PG5_1") (pintype "bidirectional"))
    )
    (net (code "138") (name "unconnected-(U1-(OC1A{slash}PCINT5)PB5-Pad24)") (class "Default")
      (node (ref "U1") (pin "24") (pinfunction "(OC1A/PCINT5)PB5_24") (pintype "bidirectional"))
    )
    (net (code "139") (name "unconnected-(U1-(OC1B{slash}PCINT6)PB6-Pad25)") (class "Default")
      (node (ref "U1") (pin "25") (pinfunction "(OC1B/PCINT6)PB6_25") (pintype "bidirectional"))
    )
    (net (code "140") (name "unconnected-(U1-(OC2A{slash}PCINT4)PB4-Pad23)") (class "Default")
      (node (ref "U1") (pin "23") (pinfunction "(OC2A/PCINT4)PB4_23") (pintype "bidirectional"))
    )
    (net (code "141") (name "unconnected-(U1-(OC3A{slash}AIN1)PE3-Pad5)") (class "Default")
      (node (ref "U1") (pin "5") (pinfunction "(OC3A/AIN1)PE3_5") (pintype "bidirectional"))
    )
    (net (code "142") (name "unconnected-(U1-(OC3B{slash}INT4)PE4-Pad6)") (class "Default")
      (node (ref "U1") (pin "6") (pinfunction "(OC3B/INT4)PE4_6") (pintype "bidirectional"))
    )
    (net (code "143") (name "unconnected-(U1-(OC3C{slash}INT5)PE5-Pad7)") (class "Default")
      (node (ref "U1") (pin "7") (pinfunction "(OC3C/INT5)PE5_7") (pintype "bidirectional"))
    )
    (net (code "144") (name "unconnected-(U1-(RD)PG1-Pad52)") (class "Default")
      (node (ref "U1") (pin "52") (pinfunction "(RD)PG1_52") (pintype "bidirectional"))
    )
    (net (code "145") (name "unconnected-(U1-(RXD0{slash}PCIN8)PE0-Pad2)") (class "Default")
      (node (ref "U1") (pin "2") (pinfunction "(RXD0/PCIN8)PE0_2") (pintype "bidirectional"))
    )
    (net (code "146") (name "unconnected-(U1-(RXD1{slash}INT2)PD2-Pad45)") (class "Default")
      (node (ref "U1") (pin "45") (pinfunction "(RXD1/INT2)PD2_45") (pintype "bidirectional"))
    )
    (net (code "147") (name "unconnected-(U1-(SCK{slash}PCINT1)PB1-Pad20)") (class "Default")
      (node (ref "U1") (pin "20") (pinfunction "(SCK/PCINT1)PB1_20") (pintype "bidirectional"))
    )
    (net (code "148") (name "unconnected-(U1-(SCL{slash}INT0)PD0-Pad43)") (class "Default")
      (node (ref "U1") (pin "43") (pinfunction "(SCL/INT0)PD0_43") (pintype "bidirectional"))
    )
    (net (code "149") (name "unconnected-(U1-(SDA{slash}INT1)PD1-Pad44)") (class "Default")
      (node (ref "U1") (pin "44") (pinfunction "(SDA/INT1)PD1_44") (pintype "bidirectional"))
    )
    (net (code "150") (name "unconnected-(U1-(SS{slash}PCINT0)PB0-Pad19)") (class "Default")
      (node (ref "U1") (pin "19") (pinfunction "(SS/PCINT0)PB0_19") (pintype "bidirectional"))
    )
    (net (code "151") (name "unconnected-(U1-(T0)PD7-Pad50)") (class "Default")
      (node (ref "U1") (pin "50") (pinfunction "(T0)PD7_50") (pintype "bidirectional"))
    )
    (net (code "152") (name "unconnected-(U1-(T1)PD6-Pad49)") (class "Default")
      (node (ref "U1") (pin "49") (pinfunction "(T1)PD6_49") (pintype "bidirectional"))
    )
    (net (code "153") (name "unconnected-(U1-(T3{slash}INT6)PE6-Pad8)") (class "Default")
      (node (ref "U1") (pin "8") (pinfunction "(T3/INT6)PE6_8") (pintype "bidirectional"))
    )
    (net (code "154") (name "unconnected-(U1-(TOSC1)PG4-Pad29)") (class "Default")
      (node (ref "U1") (pin "29") (pinfunction "(TOSC1)PG4_29") (pintype "bidirectional"))
    )
    (net (code "155") (name "unconnected-(U1-(TOSC2)PG3-Pad28)") (class "Default")
      (node (ref "U1") (pin "28") (pinfunction "(TOSC2)PG3_28") (pintype "bidirectional"))
    )
    (net (code "156") (name "unconnected-(U1-(TXD0)PE1-Pad3)") (class "Default")
      (node (ref "U1") (pin "3") (pinfunction "(TXD0)PE1_3") (pintype "bidirectional"))
    )
    (net (code "157") (name "unconnected-(U1-(TXD1{slash}INT3)PD3-Pad46)") (class "Default")
      (node (ref "U1") (pin "46") (pinfunction "(TXD1/INT3)PD3_46") (pintype "bidirectional"))
    )
    (net (code "158") (name "unconnected-(U1-(WR)PG0-Pad51)") (class "Default")
      (node (ref "U1") (pin "51") (pinfunction "(WR)PG0_51") (pintype "bidirectional"))
    )
    (net (code "159") (name "unconnected-(U1-(XCK0{slash}AIN0)PE2-Pad4)") (class "Default")
      (node (ref "U1") (pin "4") (pinfunction "(XCK0/AIN0)PE2_4") (pintype "bidirectional"))
    )
    (net (code "160") (name "unconnected-(U1-(XCK1)PD5-Pad48)") (class "Default")
      (node (ref "U1") (pin "48") (pinfunction "(XCK1)PD5_48") (pintype "bidirectional"))
    )
    (net (code "161") (name "unconnected-(U1-PH0(RXD2)-Pad12)") (class "Default")
      (node (ref "U1") (pin "12") (pinfunction "PH0(RXD2)_12") (pintype "bidirectional"))
    )
    (net (code "162") (name "unconnected-(U1-PH1(TXD2)-Pad13)") (class "Default")
      (node (ref "U1") (pin "13") (pinfunction "PH1(TXD2)_13") (pintype "bidirectional"))
    )
    (net (code "163") (name "unconnected-(U1-PH2(XCK2)-Pad14)") (class "Default")
      (node (ref "U1") (pin "14") (pinfunction "PH2(XCK2)_14") (pintype "bidirectional"))
    )
    (net (code "164") (name "unconnected-(U1-PH3(OC4A)-Pad15)") (class "Default")
      (node (ref "U1") (pin "15") (pinfunction "PH3(OC4A)_15") (pintype "bidirectional"))
    )
    (net (code "165") (name "unconnected-(U1-PH4(OC4B)-Pad16)") (class "Default")
      (node (ref "U1") (pin "16") (pinfunction "PH4(OC4B)_16") (pintype "bidirectional"))
    )
    (net (code "166") (name "unconnected-(U1-PH5(OC4C)-Pad17)") (class "Default")
      (node (ref "U1") (pin "17") (pinfunction "PH5(OC4C)_17") (pintype "bidirectional"))
    )
    (net (code "167") (name "unconnected-(U1-PH6(OC2B)-Pad18)") (class "Default")
      (node (ref "U1") (pin "18") (pinfunction "PH6(OC2B)_18") (pintype "bidirectional"))
    )
    (net (code "168") (name "unconnected-(U1-PH7(T4)-Pad27)") (class "Default")
      (node (ref "U1") (pin "27") (pinfunction "PH7(T4)_27") (pintype "bidirectional"))
    )
    (net (code "169") (name "unconnected-(U1-PJ0(RXD3{slash}PCINT9)-Pad63)") (class "Default")
      (node (ref "U1") (pin "63") (pinfunction "PJ0(RXD3/PCINT9)_63") (pintype "bidirectional"))
    )
    (net (code "170") (name "unconnected-(U1-PJ1(TXD3{slash}PCINT10)-Pad64)") (class "Default")
      (node (ref "U1") (pin "64") (pinfunction "PJ1(TXD3/PCINT10)_64") (pintype "bidirectional"))
    )
    (net (code "171") (name "unconnected-(U1-PJ2(XCK3{slash}PCINT11)-Pad65)") (class "Default")
      (node (ref "U1") (pin "65") (pinfunction "PJ2(XCK3/PCINT11)_65") (pintype "bidirectional"))
    )
    (net (code "172") (name "unconnected-(U1-PJ3(PCINT12)-Pad66)") (class "Default")
      (node (ref "U1") (pin "66") (pinfunction "PJ3(PCINT12)_66") (pintype "bidirectional"))
    )
    (net (code "173") (name "unconnected-(U1-PJ4(PCINT13)-Pad67)") (class "Default")
      (node (ref "U1") (pin "67") (pinfunction "PJ4(PCINT13)_67") (pintype "bidirectional"))
    )
    (net (code "174") (name "unconnected-(U1-PJ5(PCINT14)-Pad68)") (class "Default")
      (node (ref "U1") (pin "68") (pinfunction "PJ5(PCINT14)_68") (pintype "bidirectional"))
    )
    (net (code "175") (name "unconnected-(U1-PJ6(PCINT15)-Pad69)") (class "Default")
      (node (ref "U1") (pin "69") (pinfunction "PJ6(PCINT15)_69") (pintype "bidirectional"))
    )
    (net (code "176") (name "unconnected-(U1-PJ7-Pad79)") (class "Default")
      (node (ref "U1") (pin "79") (pinfunction "PJ7_79") (pintype "bidirectional"))
    )
    (net (code "177") (name "unconnected-(U1-PK0(ADC8{slash}PCINT16)-Pad89)") (class "Default")
      (node (ref "U1") (pin "89") (pinfunction "PK0(ADC8/PCINT16)_89") (pintype "bidirectional"))
    )
    (net (code "178") (name "unconnected-(U1-PK1(ADC9{slash}PCINT17)-Pad88)") (class "Default")
      (node (ref "U1") (pin "88") (pinfunction "PK1(ADC9/PCINT17)_88") (pintype "bidirectional"))
    )
    (net (code "179") (name "unconnected-(U1-PK2(ADC10{slash}PCINT18)-Pad87)") (class "Default")
      (node (ref "U1") (pin "87") (pinfunction "PK2(ADC10/PCINT18)_87") (pintype "bidirectional"))
    )
    (net (code "180") (name "unconnected-(U1-PK3(ADC11{slash}PCINT19)-Pad86)") (class "Default")
      (node (ref "U1") (pin "86") (pinfunction "PK3(ADC11/PCINT19)_86") (pintype "bidirectional"))
    )
    (net (code "181") (name "unconnected-(U1-PK4(ADC12{slash}PCINT20)-Pad85)") (class "Default")
      (node (ref "U1") (pin "85") (pinfunction "PK4(ADC12/PCINT20)_85") (pintype "bidirectional"))
    )
    (net (code "182") (name "unconnected-(U1-PK5(ADC13{slash}PCINT21)-Pad84)") (class "Default")
      (node (ref "U1") (pin "84") (pinfunction "PK5(ADC13/PCINT21)_84") (pintype "bidirectional"))
    )
    (net (code "183") (name "unconnected-(U1-PK6(ADC14{slash}PCINT22)-Pad83)") (class "Default")
      (node (ref "U1") (pin "83") (pinfunction "PK6(ADC14/PCINT22)_83") (pintype "bidirectional"))
    )
    (net (code "184") (name "unconnected-(U1-PK7(ADC15{slash}PCINT23)-Pad82)") (class "Default")
      (node (ref "U1") (pin "82") (pinfunction "PK7(ADC15/PCINT23)_82") (pintype "bidirectional"))
    )
    (net (code "185") (name "unconnected-(U1-PL0(ICP4)-Pad35)") (class "Default")
      (node (ref "U1") (pin "35") (pinfunction "PL0(ICP4)_35") (pintype "bidirectional"))
    )
    (net (code "186") (name "unconnected-(U1-PL1(ICP5)-Pad36)") (class "Default")
      (node (ref "U1") (pin "36") (pinfunction "PL1(ICP5)_36") (pintype "bidirectional"))
    )
    (net (code "187") (name "unconnected-(U1-PL2(T5)-Pad37)") (class "Default")
      (node (ref "U1") (pin "37") (pinfunction "PL2(T5)_37") (pintype "bidirectional"))
    )
    (net (code "188") (name "unconnected-(U1-PL3(OC5A)-Pad38)") (class "Default")
      (node (ref "U1") (pin "38") (pinfunction "PL3(OC5A)_38") (pintype "bidirectional"))
    )
    (net (code "189") (name "unconnected-(U1-PL4(OC5B)-Pad39)") (class "Default")
      (node (ref "U1") (pin "39") (pinfunction "PL4(OC5B)_39") (pintype "bidirectional"))
    )
    (net (code "190") (name "unconnected-(U1-PL5(OC5C)-Pad40)") (class "Default")
      (node (ref "U1") (pin "40") (pinfunction "PL5(OC5C)_40") (pintype "bidirectional"))
    )
    (net (code "191") (name "unconnected-(U1-PL6-Pad41)") (class "Default")
      (node (ref "U1") (pin "41") (pinfunction "PL6_41") (pintype "bidirectional"))
    )
    (net (code "192") (name "unconnected-(U1-PL7-Pad42)") (class "Default")
      (node (ref "U1") (pin "42") (pinfunction "PL7_42") (pintype "bidirectional"))
    )
    (net (code "193") (name "unconnected-(U2-BP-Pad4)") (class "Default")
      (node (ref "U2") (pin "4") (pinfunction "BP_4") (pintype "input"))
    )
  )
)
